# ASD2841.net
KiCad netlist of a schematic drawn in EAGLE
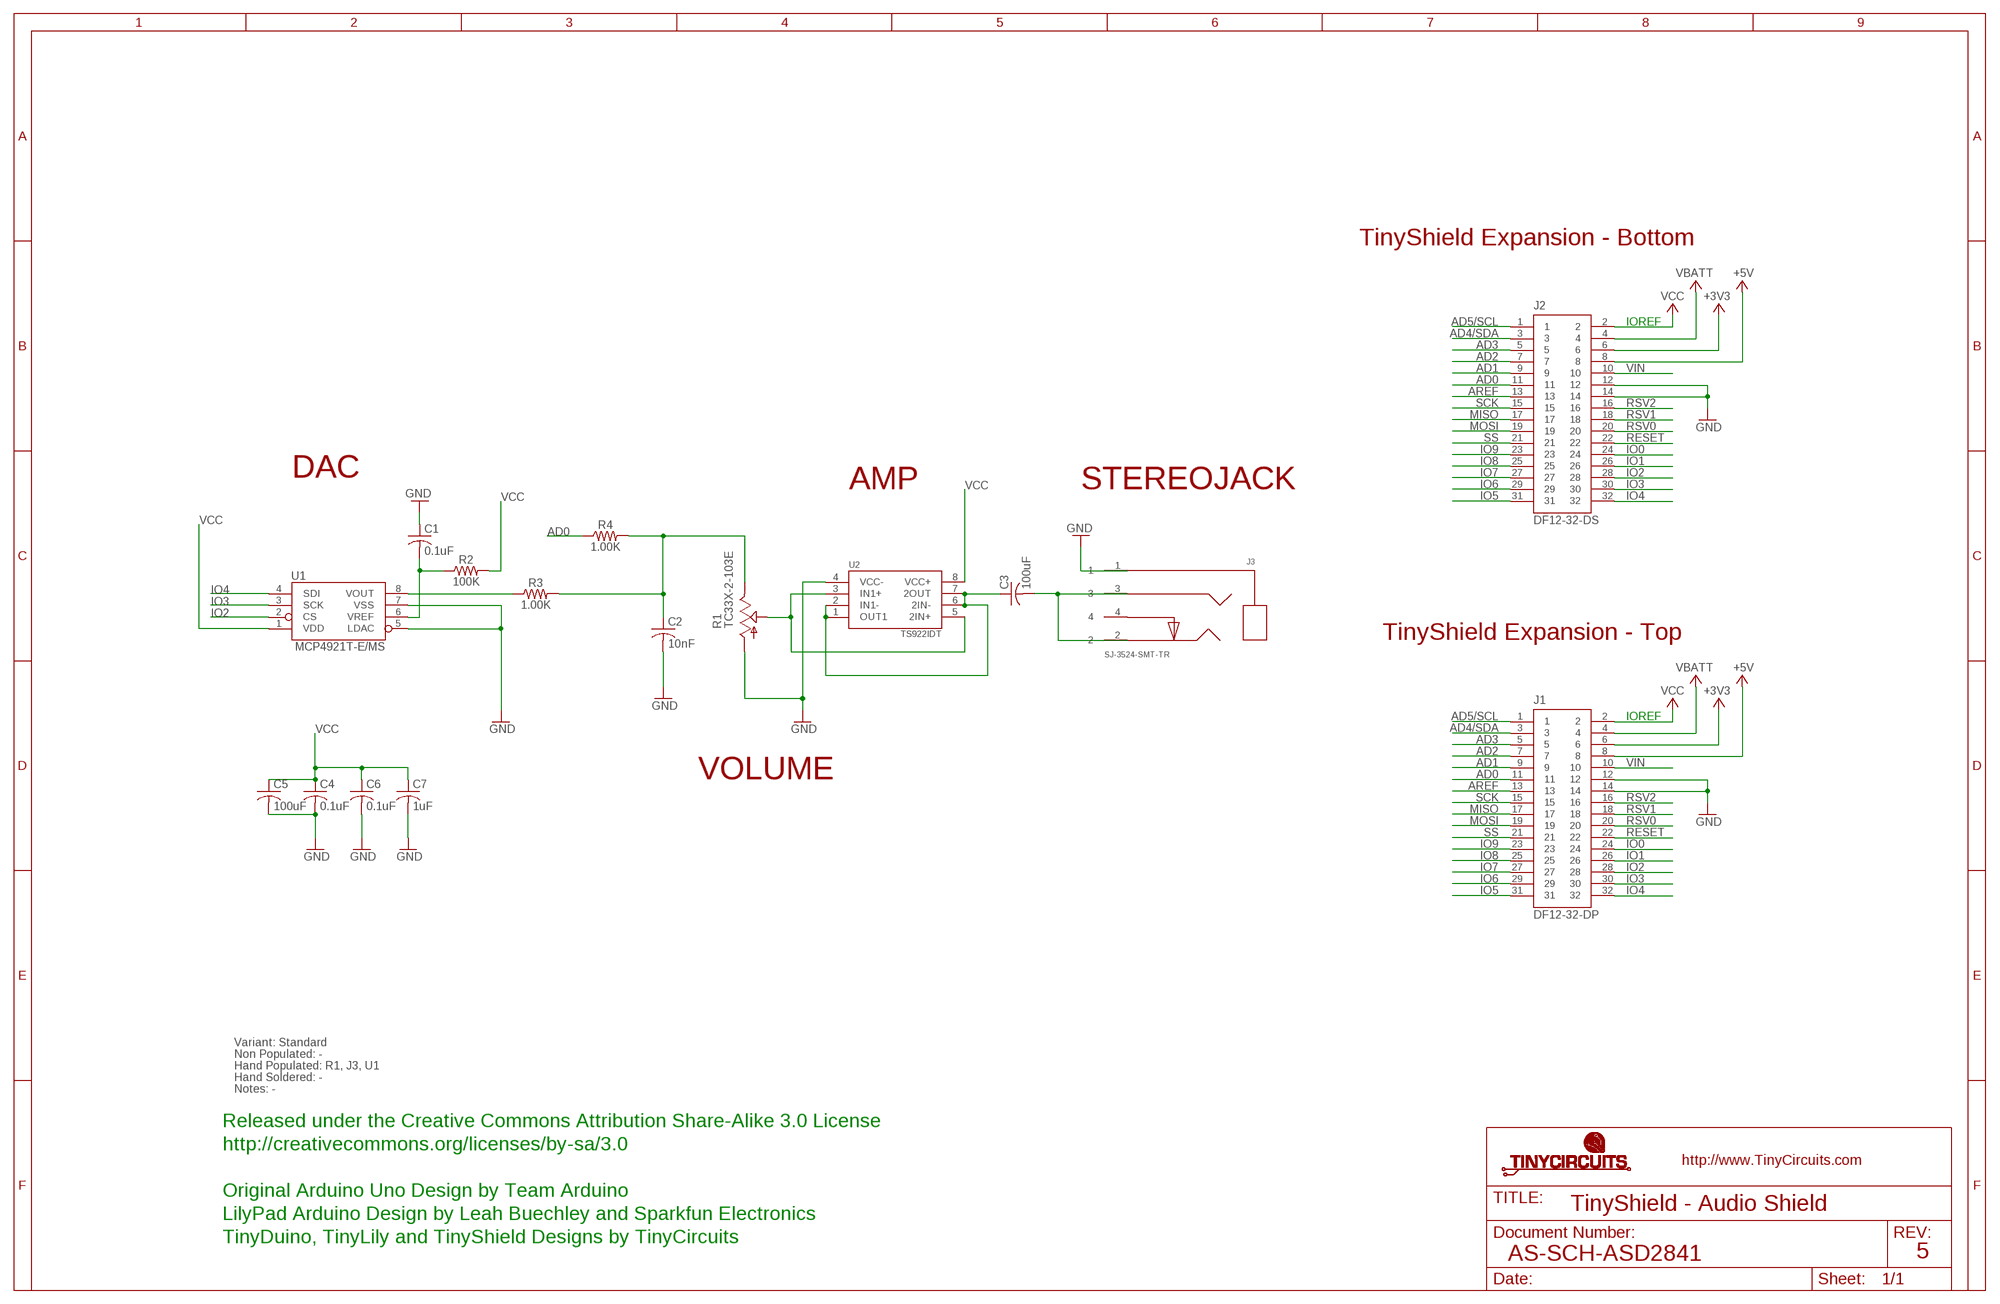
[diagram p0: schematic, sheet 1]

(export (version "E")
  (design (tool "Eeschema 10.0.6"))
  (components
    (comp (ref "C1")
      (value "0.1uF")
      (footprint "eagle-import:C0402")
      (fields (field (name "PARTNO") "AS-ITM-00008"))
      (libsource (lib "eagle-import") (part "AS-ITM-00008"))
    )
    (comp (ref "C2")
      (value "10nF")
      (footprint "eagle-import:C0402")
      (fields (field (name "PARTNO") "AS-ITM-00084"))
      (libsource (lib "eagle-import") (part "AS-ITM-00084"))
    )
    (comp (ref "C3")
      (value "100uF")
      (footprint "eagle-import:C1206")
      (fields (field (name "PARTNO") "AS-ITM-00095"))
      (libsource (lib "eagle-import") (part "AS-ITM-00095"))
    )
    (comp (ref "C4")
      (value "0.1uF")
      (footprint "eagle-import:C0402")
      (fields (field (name "PARTNO") "AS-ITM-00008"))
      (libsource (lib "eagle-import") (part "AS-ITM-00008"))
    )
    (comp (ref "C5")
      (value "100uF")
      (footprint "eagle-import:C1206")
      (fields (field (name "PARTNO") "AS-ITM-00095"))
      (libsource (lib "eagle-import") (part "AS-ITM-00095"))
    )
    (comp (ref "C6")
      (value "0.1uF")
      (footprint "eagle-import:C0402")
      (fields (field (name "PARTNO") "AS-ITM-00008") (field (name "PARTNO_1") "AS-ITM-00008"))
      (libsource (lib "eagle-import") (part "AS-ITM-00008"))
    )
    (comp (ref "C7")
      (value "1uF")
      (footprint "eagle-import:C0402")
      (fields (field (name "PARTNO") "AS-ITM-00105") (field (name "PARTNO_1") "AS-ITM-00105"))
      (libsource (lib "eagle-import") (part "AS-ITM-00105"))
    )
    (comp (ref "J1")
      (value "DF12-32-DP")
      (footprint "eagle-import:DF12-32-DP")
      (fields (field (name "PARTNO") "AS-ITM-00015") (field (name "PARTNO_1") "AS-ITM-00015"))
      (libsource (lib "eagle-import") (part "AS-ITM-00015"))
    )
    (comp (ref "J2")
      (value "DF12-32-DS")
      (footprint "eagle-import:DF12-32-DS")
      (fields (field (name "PARTNO") "AS-ITM-00012") (field (name "PARTNO_1") "AS-ITM-00012"))
      (libsource (lib "eagle-import") (part "AS-ITM-00012"))
    )
    (comp (ref "J3")
      (value "SJ-3524-SMT-TR")
      (footprint "eagle-import:SJ-3524-SMT-TR")
      (fields (field (name "PARTNO") "AS-ITM-00094"))
      (libsource (lib "eagle-import") (part "AS-ITM-00094"))
    )
    (comp (ref "R1")
      (value "TC33X-2-103E")
      (footprint "eagle-import:TC33X-2-104E")
      (fields (field (name "PARTNO") "AS-ITM-00187"))
      (libsource (lib "eagle-import") (part "AS-ITM-00187"))
    )
    (comp (ref "R2")
      (value "100K")
      (footprint "eagle-import:0402")
      (fields (field (name "PARTNO") "AS-ITM-00004"))
      (libsource (lib "eagle-import") (part "AS-ITM-00004"))
    )
    (comp (ref "R3")
      (value "1.00K")
      (footprint "eagle-import:0402")
      (fields (field (name "PARTNO") "AS-ITM-00003"))
      (libsource (lib "eagle-import") (part "AS-ITM-00003"))
    )
    (comp (ref "R4")
      (value "1.00K")
      (footprint "eagle-import:0402")
      (fields (field (name "PARTNO") "AS-ITM-00003"))
      (libsource (lib "eagle-import") (part "AS-ITM-00003"))
    )
    (comp (ref "U1")
      (value "MCP4921T-E/MS")
      (footprint "eagle-import:MSOP8")
      (fields (field (name "PARTNO") "AS-ITM-00091"))
      (libsource (lib "eagle-import") (part "AS-ITM-00091"))
    )
    (comp (ref "U2")
      (value "TS922IDT")
      (footprint "eagle-import:SO-08")
      (fields (field (name "PARTNO") "AS-ITM-00092"))
      (libsource (lib "eagle-import") (part "AS-ITM-00092"))
    )
  )
  (nets
    (net (code "1") (name "+3V3") (class "Default")
      (node (ref "J1") (pin "6") (pinfunction "6_6") (pintype "bidirectional"))
      (node (ref "J2") (pin "6") (pinfunction "6_6") (pintype "bidirectional"))
    )
    (net (code "2") (name "+5V") (class "Default")
      (node (ref "J1") (pin "8") (pinfunction "8_8") (pintype "bidirectional"))
      (node (ref "J2") (pin "8") (pinfunction "8_8") (pintype "bidirectional"))
    )
    (net (code "3") (name "/AD0") (class "Default")
      (node (ref "J1") (pin "11") (pinfunction "11_11") (pintype "bidirectional"))
      (node (ref "J2") (pin "11") (pinfunction "11_11") (pintype "bidirectional"))
      (node (ref "R4") (pin "1") (pinfunction "1_1") (pintype "passive"))
    )
    (net (code "4") (name "/AD1") (class "Default")
      (node (ref "J1") (pin "9") (pinfunction "9_9") (pintype "bidirectional"))
      (node (ref "J2") (pin "9") (pinfunction "9_9") (pintype "bidirectional"))
    )
    (net (code "5") (name "/AD2") (class "Default")
      (node (ref "J1") (pin "7") (pinfunction "7_7") (pintype "bidirectional"))
      (node (ref "J2") (pin "7") (pinfunction "7_7") (pintype "bidirectional"))
    )
    (net (code "6") (name "/AD3") (class "Default")
      (node (ref "J1") (pin "5") (pinfunction "5_5") (pintype "bidirectional"))
      (node (ref "J2") (pin "5") (pinfunction "5_5") (pintype "bidirectional"))
    )
    (net (code "7") (name "/AD4{slash}SDA") (class "Default")
      (node (ref "J1") (pin "3") (pinfunction "3_3") (pintype "bidirectional"))
      (node (ref "J2") (pin "3") (pinfunction "3_3") (pintype "bidirectional"))
    )
    (net (code "8") (name "/AD5{slash}SCL") (class "Default")
      (node (ref "J1") (pin "1") (pinfunction "1_1") (pintype "bidirectional"))
      (node (ref "J2") (pin "1") (pinfunction "1_1") (pintype "bidirectional"))
    )
    (net (code "9") (name "/AREF") (class "Default")
      (node (ref "J1") (pin "13") (pinfunction "13_13") (pintype "bidirectional"))
      (node (ref "J2") (pin "13") (pinfunction "13_13") (pintype "bidirectional"))
    )
    (net (code "10") (name "/IO0") (class "Default")
      (node (ref "J1") (pin "24") (pinfunction "24_24") (pintype "bidirectional"))
      (node (ref "J2") (pin "24") (pinfunction "24_24") (pintype "bidirectional"))
    )
    (net (code "11") (name "/IO1") (class "Default")
      (node (ref "J1") (pin "26") (pinfunction "26_26") (pintype "bidirectional"))
      (node (ref "J2") (pin "26") (pinfunction "26_26") (pintype "bidirectional"))
    )
    (net (code "12") (name "/IO2") (class "Default")
      (node (ref "J1") (pin "28") (pinfunction "28_28") (pintype "bidirectional"))
      (node (ref "J2") (pin "28") (pinfunction "28_28") (pintype "bidirectional"))
      (node (ref "U1") (pin "2") (pinfunction "CS_2") (pintype "bidirectional"))
    )
    (net (code "13") (name "/IO3") (class "Default")
      (node (ref "J1") (pin "30") (pinfunction "30_30") (pintype "bidirectional"))
      (node (ref "J2") (pin "30") (pinfunction "30_30") (pintype "bidirectional"))
      (node (ref "U1") (pin "3") (pinfunction "SCK_3") (pintype "bidirectional"))
    )
    (net (code "14") (name "/IO4") (class "Default")
      (node (ref "J1") (pin "32") (pinfunction "32_32") (pintype "bidirectional"))
      (node (ref "J2") (pin "32") (pinfunction "32_32") (pintype "bidirectional"))
      (node (ref "U1") (pin "4") (pinfunction "SDI_4") (pintype "bidirectional"))
    )
    (net (code "15") (name "/IO5") (class "Default")
      (node (ref "J1") (pin "31") (pinfunction "31_31") (pintype "bidirectional"))
      (node (ref "J2") (pin "31") (pinfunction "31_31") (pintype "bidirectional"))
    )
    (net (code "16") (name "/IO6") (class "Default")
      (node (ref "J1") (pin "29") (pinfunction "29_29") (pintype "bidirectional"))
      (node (ref "J2") (pin "29") (pinfunction "29_29") (pintype "bidirectional"))
    )
    (net (code "17") (name "/IO7") (class "Default")
      (node (ref "J1") (pin "27") (pinfunction "27_27") (pintype "bidirectional"))
      (node (ref "J2") (pin "27") (pinfunction "27_27") (pintype "bidirectional"))
    )
    (net (code "18") (name "/IO8") (class "Default")
      (node (ref "J1") (pin "25") (pinfunction "25_25") (pintype "bidirectional"))
      (node (ref "J2") (pin "25") (pinfunction "25_25") (pintype "bidirectional"))
    )
    (net (code "19") (name "/IO9") (class "Default")
      (node (ref "J1") (pin "23") (pinfunction "23_23") (pintype "bidirectional"))
      (node (ref "J2") (pin "23") (pinfunction "23_23") (pintype "bidirectional"))
    )
    (net (code "20") (name "/MISO") (class "Default")
      (node (ref "J1") (pin "17") (pinfunction "17_17") (pintype "bidirectional"))
      (node (ref "J2") (pin "17") (pinfunction "17_17") (pintype "bidirectional"))
    )
    (net (code "21") (name "/MOSI") (class "Default")
      (node (ref "J1") (pin "19") (pinfunction "19_19") (pintype "bidirectional"))
      (node (ref "J2") (pin "19") (pinfunction "19_19") (pintype "bidirectional"))
    )
    (net (code "22") (name "/RESET") (class "Default")
      (node (ref "J1") (pin "22") (pinfunction "22_22") (pintype "bidirectional"))
      (node (ref "J2") (pin "22") (pinfunction "22_22") (pintype "bidirectional"))
    )
    (net (code "23") (name "/RSV0") (class "Default")
      (node (ref "J1") (pin "20") (pinfunction "20_20") (pintype "bidirectional"))
      (node (ref "J2") (pin "20") (pinfunction "20_20") (pintype "bidirectional"))
    )
    (net (code "24") (name "/RSV1") (class "Default")
      (node (ref "J1") (pin "18") (pinfunction "18_18") (pintype "bidirectional"))
      (node (ref "J2") (pin "18") (pinfunction "18_18") (pintype "bidirectional"))
    )
    (net (code "25") (name "/RSV2") (class "Default")
      (node (ref "J1") (pin "16") (pinfunction "16_16") (pintype "bidirectional"))
      (node (ref "J2") (pin "16") (pinfunction "16_16") (pintype "bidirectional"))
    )
    (net (code "26") (name "/SCK") (class "Default")
      (node (ref "J1") (pin "15") (pinfunction "15_15") (pintype "bidirectional"))
      (node (ref "J2") (pin "15") (pinfunction "15_15") (pintype "bidirectional"))
    )
    (net (code "27") (name "/SS") (class "Default")
      (node (ref "J1") (pin "21") (pinfunction "21_21") (pintype "bidirectional"))
      (node (ref "J2") (pin "21") (pinfunction "21_21") (pintype "bidirectional"))
    )
    (net (code "28") (name "/VIN") (class "Default")
      (node (ref "J1") (pin "10") (pinfunction "10_10") (pintype "bidirectional"))
      (node (ref "J2") (pin "10") (pinfunction "10_10") (pintype "bidirectional"))
    )
    (net (code "29") (name "GND") (class "Default")
      (node (ref "C1") (pin "1") (pinfunction "1_1") (pintype "passive"))
      (node (ref "C2") (pin "2") (pinfunction "2_2") (pintype "passive"))
      (node (ref "C4") (pin "2") (pinfunction "2_2") (pintype "passive"))
      (node (ref "C5") (pin "2") (pinfunction "2_2") (pintype "passive"))
      (node (ref "C6") (pin "2") (pinfunction "2_2") (pintype "passive"))
      (node (ref "C7") (pin "2") (pinfunction "2_2") (pintype "passive"))
      (node (ref "J1") (pin "12") (pinfunction "12_12") (pintype "bidirectional"))
      (node (ref "J1") (pin "14") (pinfunction "14_14") (pintype "bidirectional"))
      (node (ref "J2") (pin "12") (pinfunction "12_12") (pintype "bidirectional"))
      (node (ref "J2") (pin "14") (pinfunction "14_14") (pintype "bidirectional"))
      (node (ref "J3") (pin "1") (pinfunction "1_1") (pintype "bidirectional"))
      (node (ref "R1") (pin "1") (pinfunction "A_1") (pintype "passive"))
      (node (ref "U1") (pin "5") (pinfunction "LDAC_5") (pintype "bidirectional"))
      (node (ref "U1") (pin "7") (pinfunction "VSS_7") (pintype "bidirectional"))
      (node (ref "U2") (pin "4") (pinfunction "VCC-_4") (pintype "bidirectional"))
    )
    (net (code "30") (name "Net-(C3-Pad2)") (class "Default")
      (node (ref "C3") (pin "2") (pinfunction "2_2") (pintype "passive"))
      (node (ref "J3") (pin "2") (pinfunction "2_2") (pintype "bidirectional"))
      (node (ref "J3") (pin "3") (pinfunction "3_3") (pintype "bidirectional"))
    )
    (net (code "31") (name "Net-(R1-E)") (class "Default")
      (node (ref "C2") (pin "1") (pinfunction "1_1") (pintype "passive"))
      (node (ref "R1") (pin "3") (pinfunction "E_3") (pintype "passive"))
      (node (ref "R3") (pin "2") (pinfunction "2_2") (pintype "passive"))
      (node (ref "R4") (pin "2") (pinfunction "2_2") (pintype "passive"))
    )
    (net (code "32") (name "Net-(R1-S)") (class "Default")
      (node (ref "R1") (pin "2") (pinfunction "S_2") (pintype "passive"))
      (node (ref "U2") (pin "3") (pinfunction "IN1+_3") (pintype "bidirectional"))
      (node (ref "U2") (pin "5") (pinfunction "2IN+_5") (pintype "bidirectional"))
    )
    (net (code "33") (name "Net-(U1-VOUT)") (class "Default")
      (node (ref "R3") (pin "1") (pinfunction "1_1") (pintype "passive"))
      (node (ref "U1") (pin "8") (pinfunction "VOUT_8") (pintype "bidirectional"))
    )
    (net (code "34") (name "Net-(U1-VREF)") (class "Default")
      (node (ref "C1") (pin "2") (pinfunction "2_2") (pintype "passive"))
      (node (ref "R2") (pin "1") (pinfunction "1_1") (pintype "passive"))
      (node (ref "U1") (pin "6") (pinfunction "VREF_6") (pintype "bidirectional"))
    )
    (net (code "35") (name "Net-(U2-2IN-)") (class "Default")
      (node (ref "C3") (pin "1") (pinfunction "1_1") (pintype "passive"))
      (node (ref "U2") (pin "1") (pinfunction "OUT1_1") (pintype "bidirectional"))
      (node (ref "U2") (pin "2") (pinfunction "IN1-_2") (pintype "bidirectional"))
      (node (ref "U2") (pin "6") (pinfunction "2IN-_6") (pintype "bidirectional"))
      (node (ref "U2") (pin "7") (pinfunction "2OUT_7") (pintype "bidirectional"))
    )
    (net (code "36") (name "VBATT") (class "Default")
      (node (ref "J1") (pin "4") (pinfunction "4_4") (pintype "bidirectional"))
      (node (ref "J2") (pin "4") (pinfunction "4_4") (pintype "bidirectional"))
    )
    (net (code "37") (name "VCC") (class "Default")
      (node (ref "C4") (pin "1") (pinfunction "1_1") (pintype "passive"))
      (node (ref "C5") (pin "1") (pinfunction "1_1") (pintype "passive"))
      (node (ref "C6") (pin "1") (pinfunction "1_1") (pintype "passive"))
      (node (ref "C7") (pin "1") (pinfunction "1_1") (pintype "passive"))
      (node (ref "J1") (pin "2") (pinfunction "2_2") (pintype "bidirectional"))
      (node (ref "J2") (pin "2") (pinfunction "2_2") (pintype "bidirectional"))
      (node (ref "R2") (pin "2") (pinfunction "2_2") (pintype "passive"))
      (node (ref "U1") (pin "1") (pinfunction "VDD_1") (pintype "bidirectional"))
      (node (ref "U2") (pin "8") (pinfunction "VCC+_8") (pintype "bidirectional"))
    )
    (net (code "38") (name "unconnected-(J3-Pad4)") (class "Default")
      (node (ref "J3") (pin "4") (pinfunction "4_4") (pintype "bidirectional"))
    )
  )
)
